# untitled.net
KiCad netlist of a schematic drawn in EAGLE
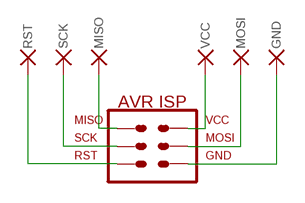
[diagram p0: schematic, sheet 1]

(export (version "E")
  (design (tool "Eeschema 10.0.6"))
  (components
    (comp (ref "GND")
      (value "GND")
      (footprint "eagle-import:POGO_PIN_P50-XX_HORIZONTALLY")
      (libsource (lib "eagle-import") (part "POGO_PIN_P50-XX_HORIZONTALLY"))
    )
    (comp (ref "MISO")
      (value "MISO")
      (footprint "eagle-import:POGO_PIN_P50-XX_HORIZONTALLY")
      (libsource (lib "eagle-import") (part "POGO_PIN_P50-XX_HORIZONTALLY"))
    )
    (comp (ref "MOSI")
      (value "MOSI")
      (footprint "eagle-import:POGO_PIN_P50-XX_HORIZONTALLY")
      (libsource (lib "eagle-import") (part "POGO_PIN_P50-XX_HORIZONTALLY"))
    )
    (comp (ref "RST")
      (value "RST")
      (footprint "eagle-import:POGO_PIN_P50-XX_HORIZONTALLY")
      (libsource (lib "eagle-import") (part "POGO_PIN_P50-XX_HORIZONTALLY"))
    )
    (comp (ref "SCK")
      (value "SCK")
      (footprint "eagle-import:POGO_PIN_P50-XX_HORIZONTALLY")
      (libsource (lib "eagle-import") (part "POGO_PIN_P50-XX_HORIZONTALLY"))
    )
    (comp (ref "VCC")
      (value "VCC")
      (footprint "eagle-import:POGO_PIN_P50-XX_HORIZONTALLY")
      (libsource (lib "eagle-import") (part "POGO_PIN_P50-XX_HORIZONTALLY"))
    )
    (comp (ref "X1")
      (value "AVR-ISP_6X_IDC_LOCK_EDGE_PCB")
      (footprint "eagle-import:AVR-ISP-6_EDGE_PCB")
      (libsource (lib "eagle-import") (part "AVR-ISP_6X_IDC_LOCK_EDGE_PCB"))
    )
  )
  (nets
    (net (code "1") (name "Net-(GND-P)") (class "Default")
      (node (ref "GND") (pin "P$1") (pinfunction "P_P$1") (pintype "passive"))
      (node (ref "X1") (pin "GND") (pinfunction "GND_GND") (pintype "passive"))
    )
    (net (code "2") (name "Net-(MISO-P)") (class "Default")
      (node (ref "MISO") (pin "P$1") (pinfunction "P_P$1") (pintype "passive"))
      (node (ref "X1") (pin "MISO") (pinfunction "MISO_MISO") (pintype "passive"))
    )
    (net (code "3") (name "Net-(MOSI-P)") (class "Default")
      (node (ref "MOSI") (pin "P$1") (pinfunction "P_P$1") (pintype "passive"))
      (node (ref "X1") (pin "MOSI") (pinfunction "MOSI_MOSI") (pintype "passive"))
    )
    (net (code "4") (name "Net-(RST-P)") (class "Default")
      (node (ref "RST") (pin "P$1") (pinfunction "P_P$1") (pintype "passive"))
      (node (ref "X1") (pin "RST") (pinfunction "RST_RST") (pintype "passive"))
    )
    (net (code "5") (name "Net-(SCK-P)") (class "Default")
      (node (ref "SCK") (pin "P$1") (pinfunction "P_P$1") (pintype "passive"))
      (node (ref "X1") (pin "SCK") (pinfunction "SCK_SCK") (pintype "passive"))
    )
    (net (code "6") (name "Net-(VCC-P)") (class "Default")
      (node (ref "VCC") (pin "P$1") (pinfunction "P_P$1") (pintype "passive"))
      (node (ref "X1") (pin "VCC") (pinfunction "VCC_VCC") (pintype "passive"))
    )
  )
)
